# automatic_board.net
KiCad netlist of a schematic drawn in EAGLE
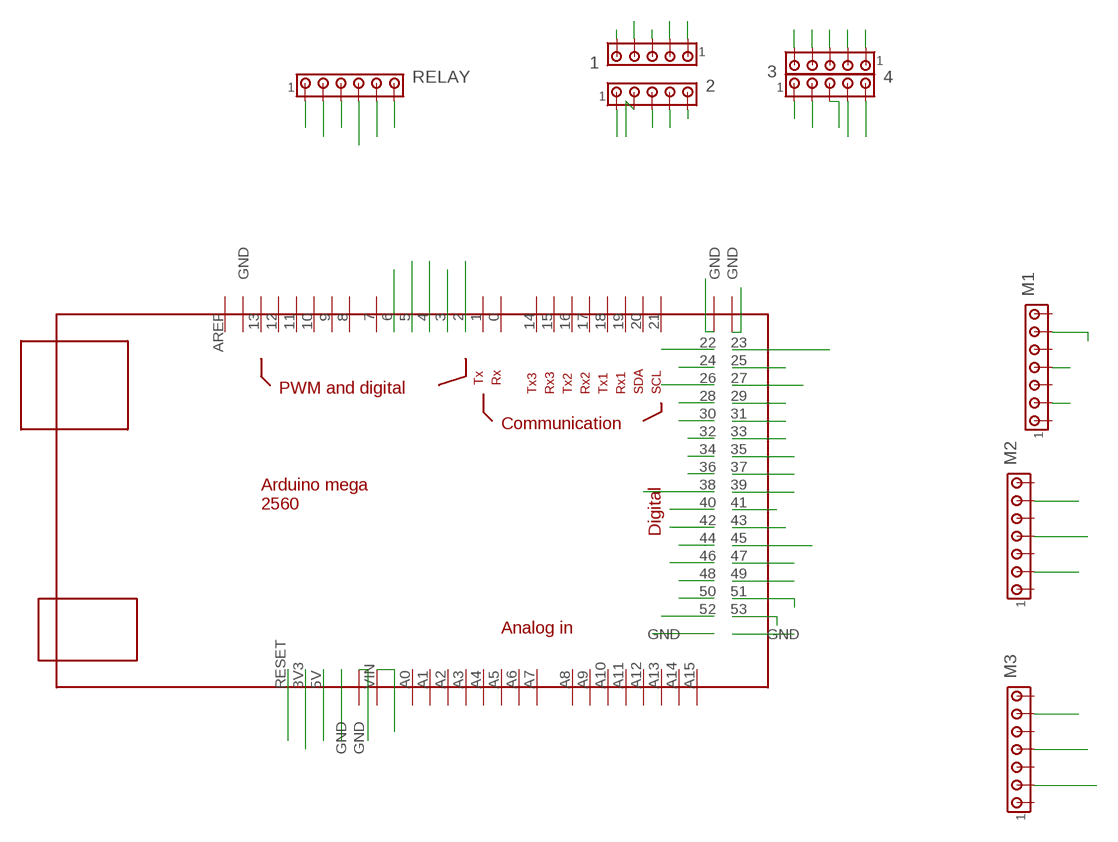
[diagram p0: schematic, sheet 1]

(export (version "E")
  (design (tool "Eeschema 10.0.6"))
  (components
    (comp (ref "1")
      (value "MTA05-100")
      (footprint "eagle-import:10X05MTA")
      (libsource (lib "eagle-import") (part "MTA05-100"))
    )
    (comp (ref "2")
      (value "MTA05-100")
      (footprint "eagle-import:10X05MTA")
      (libsource (lib "eagle-import") (part "MTA05-100"))
    )
    (comp (ref "3")
      (value "MTA05-100")
      (footprint "eagle-import:10X05MTA")
      (libsource (lib "eagle-import") (part "MTA05-100"))
    )
    (comp (ref "4")
      (value "MTA05-100")
      (footprint "eagle-import:10X05MTA")
      (libsource (lib "eagle-import") (part "MTA05-100"))
    )
    (comp (ref "M1")
      (value "MTA07-100")
      (footprint "eagle-import:10X07MTA")
      (libsource (lib "eagle-import") (part "MTA07-100"))
    )
    (comp (ref "M2")
      (value "MTA07-100")
      (footprint "eagle-import:10X07MTA")
      (libsource (lib "eagle-import") (part "MTA07-100"))
    )
    (comp (ref "M3")
      (value "MTA07-100")
      (footprint "eagle-import:10X07MTA")
      (libsource (lib "eagle-import") (part "MTA07-100"))
    )
    (comp (ref "RELAY")
      (value "MTA06-100")
      (footprint "eagle-import:10X06MTA")
      (libsource (lib "eagle-import") (part "MTA06-100"))
    )
    (comp (ref "U$1")
      (value "MEGA_DEVICE")
      (footprint "eagle-import:MEGAOUTLINE")
      (libsource (lib "eagle-import") (part "MEGA_DEVICE"))
    )
  )
  (nets
    (net (code "1") (name "/2") (class "Default")
      (node (ref "M3") (pin "4") (pinfunction "4_4") (pintype "passive"))
      (node (ref "U$1") (pin "2") (pinfunction "2_2") (pintype "bidirectional"))
    )
    (net (code "2") (name "/3") (class "Default")
      (node (ref "M2") (pin "4") (pinfunction "4_4") (pintype "passive"))
      (node (ref "U$1") (pin "3") (pinfunction "3_3") (pintype "bidirectional"))
    )
    (net (code "3") (name "/4") (class "Default")
      (node (ref "M1") (pin "4") (pinfunction "4_4") (pintype "passive"))
      (node (ref "U$1") (pin "4") (pinfunction "4_4") (pintype "bidirectional"))
    )
    (net (code "4") (name "/22") (class "Default")
      (node (ref "M1") (pin "2") (pinfunction "2_2") (pintype "passive"))
      (node (ref "U$1") (pin "22") (pinfunction "22_22") (pintype "bidirectional"))
    )
    (net (code "5") (name "/23") (class "Default")
      (node (ref "1") (pin "5") (pinfunction "5_5") (pintype "passive"))
      (node (ref "U$1") (pin "23") (pinfunction "23_23") (pintype "bidirectional"))
    )
    (net (code "6") (name "/24") (class "Default")
      (node (ref "M1") (pin "6") (pinfunction "6_6") (pintype "passive"))
      (node (ref "U$1") (pin "24") (pinfunction "24_24") (pintype "bidirectional"))
    )
    (net (code "7") (name "/25") (class "Default")
      (node (ref "1") (pin "4") (pinfunction "4_4") (pintype "passive"))
      (node (ref "U$1") (pin "25") (pinfunction "25_25") (pintype "bidirectional"))
    )
    (net (code "8") (name "/26") (class "Default")
      (node (ref "M2") (pin "2") (pinfunction "2_2") (pintype "passive"))
      (node (ref "U$1") (pin "26") (pinfunction "26_26") (pintype "bidirectional"))
    )
    (net (code "9") (name "/27") (class "Default")
      (node (ref "1") (pin "3") (pinfunction "3_3") (pintype "passive"))
      (node (ref "U$1") (pin "27") (pinfunction "27_27") (pintype "bidirectional"))
    )
    (net (code "10") (name "/28") (class "Default")
      (node (ref "M2") (pin "6") (pinfunction "6_6") (pintype "passive"))
      (node (ref "U$1") (pin "28") (pinfunction "28_28") (pintype "bidirectional"))
    )
    (net (code "11") (name "/29") (class "Default")
      (node (ref "1") (pin "2") (pinfunction "2_2") (pintype "passive"))
      (node (ref "U$1") (pin "29") (pinfunction "29_29") (pintype "bidirectional"))
    )
    (net (code "12") (name "/30") (class "Default")
      (node (ref "M3") (pin "2") (pinfunction "2_2") (pintype "passive"))
      (node (ref "U$1") (pin "30") (pinfunction "30_30") (pintype "bidirectional"))
    )
    (net (code "13") (name "/31") (class "Default")
      (node (ref "2") (pin "4") (pinfunction "4_4") (pintype "passive"))
      (node (ref "U$1") (pin "31") (pinfunction "31_31") (pintype "bidirectional"))
    )
    (net (code "14") (name "/32") (class "Default")
      (node (ref "M3") (pin "6") (pinfunction "6_6") (pintype "passive"))
      (node (ref "U$1") (pin "32") (pinfunction "32_32") (pintype "bidirectional"))
    )
    (net (code "15") (name "/33") (class "Default")
      (node (ref "2") (pin "3") (pinfunction "3_3") (pintype "passive"))
      (node (ref "U$1") (pin "33") (pinfunction "33_33") (pintype "bidirectional"))
    )
    (net (code "16") (name "/34") (class "Default")
      (node (ref "RELAY") (pin "2") (pinfunction "2_2") (pintype "passive"))
      (node (ref "U$1") (pin "34") (pinfunction "34_34") (pintype "bidirectional"))
    )
    (net (code "17") (name "/35") (class "Default")
      (node (ref "2") (pin "2") (pinfunction "2_2") (pintype "passive"))
      (node (ref "U$1") (pin "35") (pinfunction "35_35") (pintype "bidirectional"))
    )
    (net (code "18") (name "/36") (class "Default")
      (node (ref "RELAY") (pin "3") (pinfunction "3_3") (pintype "passive"))
      (node (ref "U$1") (pin "36") (pinfunction "36_36") (pintype "bidirectional"))
    )
    (net (code "19") (name "/37") (class "Default")
      (node (ref "2") (pin "1") (pinfunction "1_1") (pintype "passive"))
      (node (ref "U$1") (pin "37") (pinfunction "37_37") (pintype "bidirectional"))
    )
    (net (code "20") (name "/38") (class "Default")
      (node (ref "RELAY") (pin "4") (pinfunction "4_4") (pintype "passive"))
      (node (ref "U$1") (pin "38") (pinfunction "38_38") (pintype "bidirectional"))
    )
    (net (code "21") (name "/39") (class "Default")
      (node (ref "3") (pin "5") (pinfunction "5_5") (pintype "passive"))
      (node (ref "U$1") (pin "39") (pinfunction "39_39") (pintype "bidirectional"))
    )
    (net (code "22") (name "/40") (class "Default")
      (node (ref "RELAY") (pin "5") (pinfunction "5_5") (pintype "passive"))
      (node (ref "U$1") (pin "40") (pinfunction "40_40") (pintype "bidirectional"))
    )
    (net (code "23") (name "/41") (class "Default")
      (node (ref "3") (pin "4") (pinfunction "4_4") (pintype "passive"))
      (node (ref "U$1") (pin "41") (pinfunction "41_41") (pintype "bidirectional"))
    )
    (net (code "24") (name "/43") (class "Default")
      (node (ref "3") (pin "3") (pinfunction "3_3") (pintype "passive"))
      (node (ref "U$1") (pin "43") (pinfunction "43_43") (pintype "bidirectional"))
    )
    (net (code "25") (name "/45") (class "Default")
      (node (ref "3") (pin "2") (pinfunction "2_2") (pintype "passive"))
      (node (ref "U$1") (pin "45") (pinfunction "45_45") (pintype "bidirectional"))
    )
    (net (code "26") (name "/47") (class "Default")
      (node (ref "4") (pin "4") (pinfunction "4_4") (pintype "passive"))
      (node (ref "U$1") (pin "47") (pinfunction "47_47") (pintype "bidirectional"))
    )
    (net (code "27") (name "/49") (class "Default")
      (node (ref "4") (pin "3") (pinfunction "3_3") (pintype "passive"))
      (node (ref "U$1") (pin "49") (pinfunction "49_49") (pintype "bidirectional"))
    )
    (net (code "28") (name "/51") (class "Default")
      (node (ref "4") (pin "2") (pinfunction "2_2") (pintype "passive"))
      (node (ref "U$1") (pin "51") (pinfunction "51_51") (pintype "bidirectional"))
    )
    (net (code "29") (name "/52") (class "Default")
      (node (ref "4") (pin "1") (pinfunction "1_1") (pintype "passive"))
      (node (ref "U$1") (pin "52") (pinfunction "52_52") (pintype "bidirectional"))
    )
    (net (code "30") (name "/GND") (class "Default")
      (node (ref "1") (pin "1") (pinfunction "1_1") (pintype "passive"))
      (node (ref "3") (pin "1") (pinfunction "1_1") (pintype "passive"))
      (node (ref "RELAY") (pin "6") (pinfunction "6_6") (pintype "passive"))
      (node (ref "U$1") (pin "GND@2") (pinfunction "GND_GND@2") (pintype "bidirectional"))
      (node (ref "U$1") (pin "GND@3") (pinfunction "GND_GND@3") (pintype "bidirectional"))
      (node (ref "U$1") (pin "GND@6") (pinfunction "GND_GND@6") (pintype "bidirectional"))
      (node (ref "U$1") (pin "GND@7") (pinfunction "GND_GND@7") (pintype "bidirectional"))
    )
    (net (code "31") (name "/VCC1") (class "Default")
      (node (ref "RELAY") (pin "1") (pinfunction "1_1") (pintype "passive"))
      (node (ref "U$1") (pin "5V") (pinfunction "5V_5V") (pintype "bidirectional"))
    )
    (net (code "32") (name "/VCC3") (class "Default")
      (node (ref "2") (pin "5") (pinfunction "5_5") (pintype "passive"))
      (node (ref "4") (pin "5") (pinfunction "5_5") (pintype "passive"))
      (node (ref "U$1") (pin "GND@5") (pinfunction "GND_GND@5") (pintype "bidirectional"))
    )
    (net (code "33") (name "unconnected-(M1-Pad1)") (class "Default")
      (node (ref "M1") (pin "1") (pinfunction "1_1") (pintype "passive"))
    )
    (net (code "34") (name "unconnected-(M1-Pad3)") (class "Default")
      (node (ref "M1") (pin "3") (pinfunction "3_3") (pintype "passive"))
    )
    (net (code "35") (name "unconnected-(M1-Pad5)") (class "Default")
      (node (ref "M1") (pin "5") (pinfunction "5_5") (pintype "passive"))
    )
    (net (code "36") (name "unconnected-(M1-Pad7)") (class "Default")
      (node (ref "M1") (pin "7") (pinfunction "7_7") (pintype "passive"))
    )
    (net (code "37") (name "unconnected-(M2-Pad1)") (class "Default")
      (node (ref "M2") (pin "1") (pinfunction "1_1") (pintype "passive"))
    )
    (net (code "38") (name "unconnected-(M2-Pad3)") (class "Default")
      (node (ref "M2") (pin "3") (pinfunction "3_3") (pintype "passive"))
    )
    (net (code "39") (name "unconnected-(M2-Pad5)") (class "Default")
      (node (ref "M2") (pin "5") (pinfunction "5_5") (pintype "passive"))
    )
    (net (code "40") (name "unconnected-(M2-Pad7)") (class "Default")
      (node (ref "M2") (pin "7") (pinfunction "7_7") (pintype "passive"))
    )
    (net (code "41") (name "unconnected-(M3-Pad1)") (class "Default")
      (node (ref "M3") (pin "1") (pinfunction "1_1") (pintype "passive"))
    )
    (net (code "42") (name "unconnected-(M3-Pad3)") (class "Default")
      (node (ref "M3") (pin "3") (pinfunction "3_3") (pintype "passive"))
    )
    (net (code "43") (name "unconnected-(M3-Pad5)") (class "Default")
      (node (ref "M3") (pin "5") (pinfunction "5_5") (pintype "passive"))
    )
    (net (code "44") (name "unconnected-(M3-Pad7)") (class "Default")
      (node (ref "M3") (pin "7") (pinfunction "7_7") (pintype "passive"))
    )
    (net (code "45") (name "unconnected-(U$1-GND-PadGND@1)") (class "Default")
      (node (ref "U$1") (pin "GND@1") (pinfunction "GND_GND@1") (pintype "bidirectional"))
    )
    (net (code "46") (name "unconnected-(U$1-GND-PadGND@4)") (class "Default")
      (node (ref "U$1") (pin "GND@4") (pinfunction "GND_GND@4") (pintype "bidirectional"))
    )
    (net (code "47") (name "unconnected-(U$1-Pad0)") (class "Default")
      (node (ref "U$1") (pin "0") (pinfunction "0_0") (pintype "bidirectional"))
    )
    (net (code "48") (name "unconnected-(U$1-Pad1)") (class "Default")
      (node (ref "U$1") (pin "1") (pinfunction "1_1") (pintype "bidirectional"))
    )
    (net (code "49") (name "unconnected-(U$1-Pad3V3)") (class "Default")
      (node (ref "U$1") (pin "3V3") (pinfunction "3V3_3V3") (pintype "bidirectional"))
    )
    (net (code "50") (name "unconnected-(U$1-Pad5)") (class "Default")
      (node (ref "U$1") (pin "5") (pinfunction "5_5") (pintype "bidirectional"))
    )
    (net (code "51") (name "unconnected-(U$1-Pad6)") (class "Default")
      (node (ref "U$1") (pin "6") (pinfunction "6_6") (pintype "bidirectional"))
    )
    (net (code "52") (name "unconnected-(U$1-Pad7)") (class "Default")
      (node (ref "U$1") (pin "7") (pinfunction "7_7") (pintype "bidirectional"))
    )
    (net (code "53") (name "unconnected-(U$1-Pad8)") (class "Default")
      (node (ref "U$1") (pin "8") (pinfunction "8_8") (pintype "bidirectional"))
    )
    (net (code "54") (name "unconnected-(U$1-Pad9)") (class "Default")
      (node (ref "U$1") (pin "9") (pinfunction "9_9") (pintype "bidirectional"))
    )
    (net (code "55") (name "unconnected-(U$1-Pad10)") (class "Default")
      (node (ref "U$1") (pin "10") (pinfunction "10_10") (pintype "bidirectional"))
    )
    (net (code "56") (name "unconnected-(U$1-Pad11)") (class "Default")
      (node (ref "U$1") (pin "11") (pinfunction "11_11") (pintype "bidirectional"))
    )
    (net (code "57") (name "unconnected-(U$1-Pad12)") (class "Default")
      (node (ref "U$1") (pin "12") (pinfunction "12_12") (pintype "bidirectional"))
    )
    (net (code "58") (name "unconnected-(U$1-Pad13)") (class "Default")
      (node (ref "U$1") (pin "13") (pinfunction "13_13") (pintype "bidirectional"))
    )
    (net (code "59") (name "unconnected-(U$1-Pad14)") (class "Default")
      (node (ref "U$1") (pin "14") (pinfunction "14_14") (pintype "bidirectional"))
    )
    (net (code "60") (name "unconnected-(U$1-Pad15)") (class "Default")
      (node (ref "U$1") (pin "15") (pinfunction "15_15") (pintype "bidirectional"))
    )
    (net (code "61") (name "unconnected-(U$1-Pad16)") (class "Default")
      (node (ref "U$1") (pin "16") (pinfunction "16_16") (pintype "bidirectional"))
    )
    (net (code "62") (name "unconnected-(U$1-Pad17)") (class "Default")
      (node (ref "U$1") (pin "17") (pinfunction "17_17") (pintype "bidirectional"))
    )
    (net (code "63") (name "unconnected-(U$1-Pad18)") (class "Default")
      (node (ref "U$1") (pin "18") (pinfunction "18_18") (pintype "bidirectional"))
    )
    (net (code "64") (name "unconnected-(U$1-Pad19)") (class "Default")
      (node (ref "U$1") (pin "19") (pinfunction "19_19") (pintype "bidirectional"))
    )
    (net (code "65") (name "unconnected-(U$1-Pad20)") (class "Default")
      (node (ref "U$1") (pin "20") (pinfunction "20_20") (pintype "bidirectional"))
    )
    (net (code "66") (name "unconnected-(U$1-Pad21)") (class "Default")
      (node (ref "U$1") (pin "21") (pinfunction "21_21") (pintype "bidirectional"))
    )
    (net (code "67") (name "unconnected-(U$1-Pad42)") (class "Default")
      (node (ref "U$1") (pin "42") (pinfunction "42_42") (pintype "bidirectional"))
    )
    (net (code "68") (name "unconnected-(U$1-Pad44)") (class "Default")
      (node (ref "U$1") (pin "44") (pinfunction "44_44") (pintype "bidirectional"))
    )
    (net (code "69") (name "unconnected-(U$1-Pad46)") (class "Default")
      (node (ref "U$1") (pin "46") (pinfunction "46_46") (pintype "bidirectional"))
    )
    (net (code "70") (name "unconnected-(U$1-Pad48)") (class "Default")
      (node (ref "U$1") (pin "48") (pinfunction "48_48") (pintype "bidirectional"))
    )
    (net (code "71") (name "unconnected-(U$1-Pad50)") (class "Default")
      (node (ref "U$1") (pin "50") (pinfunction "50_50") (pintype "bidirectional"))
    )
    (net (code "72") (name "unconnected-(U$1-Pad53)") (class "Default")
      (node (ref "U$1") (pin "53") (pinfunction "53_53") (pintype "bidirectional"))
    )
    (net (code "73") (name "unconnected-(U$1-PadA0)") (class "Default")
      (node (ref "U$1") (pin "A0") (pinfunction "A0_A0") (pintype "bidirectional"))
    )
    (net (code "74") (name "unconnected-(U$1-PadA1)") (class "Default")
      (node (ref "U$1") (pin "A1") (pinfunction "A1_A1") (pintype "bidirectional"))
    )
    (net (code "75") (name "unconnected-(U$1-PadA2)") (class "Default")
      (node (ref "U$1") (pin "A2") (pinfunction "A2_A2") (pintype "bidirectional"))
    )
    (net (code "76") (name "unconnected-(U$1-PadA3)") (class "Default")
      (node (ref "U$1") (pin "A3") (pinfunction "A3_A3") (pintype "bidirectional"))
    )
    (net (code "77") (name "unconnected-(U$1-PadA4)") (class "Default")
      (node (ref "U$1") (pin "A4") (pinfunction "A4_A4") (pintype "bidirectional"))
    )
    (net (code "78") (name "unconnected-(U$1-PadA5)") (class "Default")
      (node (ref "U$1") (pin "A5") (pinfunction "A5_A5") (pintype "bidirectional"))
    )
    (net (code "79") (name "unconnected-(U$1-PadA6)") (class "Default")
      (node (ref "U$1") (pin "A6") (pinfunction "A6_A6") (pintype "bidirectional"))
    )
    (net (code "80") (name "unconnected-(U$1-PadA7)") (class "Default")
      (node (ref "U$1") (pin "A7") (pinfunction "A7_A7") (pintype "bidirectional"))
    )
    (net (code "81") (name "unconnected-(U$1-PadA8)") (class "Default")
      (node (ref "U$1") (pin "A8") (pinfunction "A8_A8") (pintype "bidirectional"))
    )
    (net (code "82") (name "unconnected-(U$1-PadA9)") (class "Default")
      (node (ref "U$1") (pin "A9") (pinfunction "A9_A9") (pintype "bidirectional"))
    )
    (net (code "83") (name "unconnected-(U$1-PadA10)") (class "Default")
      (node (ref "U$1") (pin "A10") (pinfunction "A10_A10") (pintype "bidirectional"))
    )
    (net (code "84") (name "unconnected-(U$1-PadA11)") (class "Default")
      (node (ref "U$1") (pin "A11") (pinfunction "A11_A11") (pintype "bidirectional"))
    )
    (net (code "85") (name "unconnected-(U$1-PadA12)") (class "Default")
      (node (ref "U$1") (pin "A12") (pinfunction "A12_A12") (pintype "bidirectional"))
    )
    (net (code "86") (name "unconnected-(U$1-PadA13)") (class "Default")
      (node (ref "U$1") (pin "A13") (pinfunction "A13_A13") (pintype "bidirectional"))
    )
    (net (code "87") (name "unconnected-(U$1-PadA14)") (class "Default")
      (node (ref "U$1") (pin "A14") (pinfunction "A14_A14") (pintype "bidirectional"))
    )
    (net (code "88") (name "unconnected-(U$1-PadA15)") (class "Default")
      (node (ref "U$1") (pin "A15") (pinfunction "A15_A15") (pintype "bidirectional"))
    )
    (net (code "89") (name "unconnected-(U$1-PadAREF)") (class "Default")
      (node (ref "U$1") (pin "AREF") (pinfunction "AREF_AREF") (pintype "bidirectional"))
    )
    (net (code "90") (name "unconnected-(U$1-PadRESET)") (class "Default")
      (node (ref "U$1") (pin "RESET") (pinfunction "RESET_RESET") (pintype "bidirectional"))
    )
    (net (code "91") (name "unconnected-(U$1-PadVIN)") (class "Default")
      (node (ref "U$1") (pin "VIN") (pinfunction "VIN_VIN") (pintype "bidirectional"))
    )
  )
)
